# moodlamp.net
KiCad netlist of a schematic drawn in EAGLE
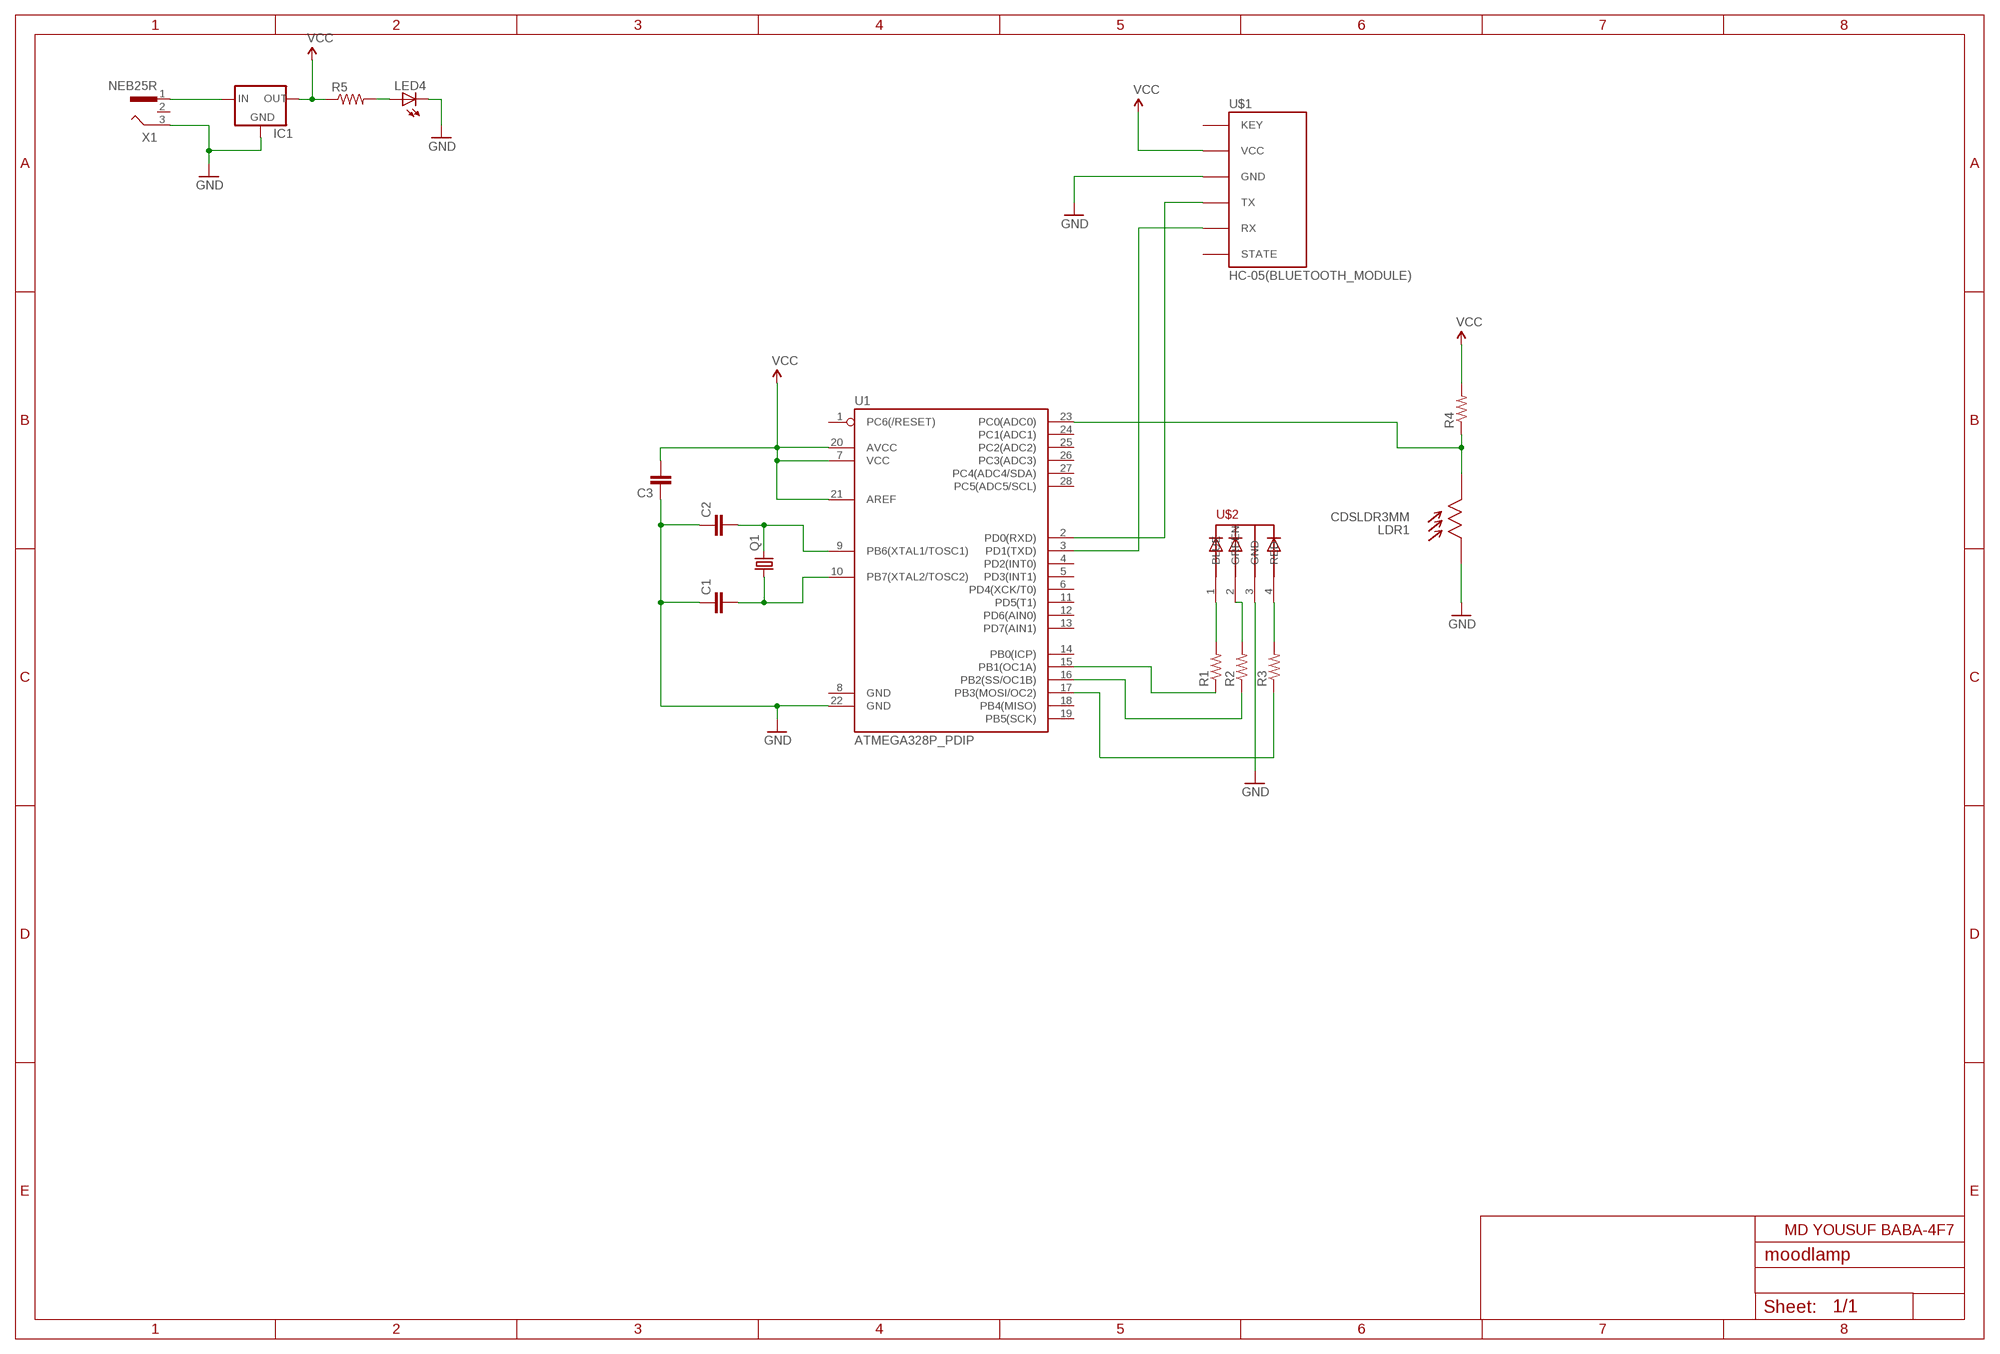
[diagram p0: schematic, sheet 1]

(export (version "E")
  (design (tool "Eeschema 10.0.6"))
  (components
    (comp (ref "C1")
      (value "C-EU025-024X044")
      (footprint "eagle-import:C025-024X044")
      (libsource (lib "eagle-import") (part "C-EU025-024X044"))
    )
    (comp (ref "C2")
      (value "C-EU025-024X044")
      (footprint "eagle-import:C025-024X044")
      (libsource (lib "eagle-import") (part "C-EU025-024X044"))
    )
    (comp (ref "C3")
      (value "C-EU025-024X044")
      (footprint "eagle-import:C025-024X044")
      (libsource (lib "eagle-import") (part "C-EU025-024X044"))
    )
    (comp (ref "IC1")
      (value "V_REG_78XX-TO-220")
      (footprint "eagle-import:TO-220-ALT")
      (libsource (lib "eagle-import") (part "V_REG_78XX-TO-220"))
    )
    (comp (ref "LDR1")
      (value "CDSLDR3MM")
      (footprint "eagle-import:LDR3MM")
      (libsource (lib "eagle-import") (part "CDSLDR3MM"))
    )
    (comp (ref "LED4")
      (value "LED3MM")
      (footprint "eagle-import:LED3MM")
      (libsource (lib "eagle-import") (part "LED3MM"))
    )
    (comp (ref "Q1")
      (value "CRYSTALHC49US")
      (footprint "eagle-import:HC49US")
      (libsource (lib "eagle-import") (part "CRYSTALHC49US"))
    )
    (comp (ref "R1")
      (value "RESISTOR0207/7")
      (footprint "eagle-import:0207_7")
      (libsource (lib "eagle-import") (part "RESISTOR0207/7"))
    )
    (comp (ref "R2")
      (value "RESISTOR0207/7")
      (footprint "eagle-import:0207_7")
      (libsource (lib "eagle-import") (part "RESISTOR0207/7"))
    )
    (comp (ref "R3")
      (value "RESISTOR0207/7")
      (footprint "eagle-import:0207_7")
      (libsource (lib "eagle-import") (part "RESISTOR0207/7"))
    )
    (comp (ref "R4")
      (value "RESISTOR0207/7")
      (footprint "eagle-import:0207_7")
      (libsource (lib "eagle-import") (part "RESISTOR0207/7"))
    )
    (comp (ref "R5")
      (value "RESISTOR0207/7")
      (footprint "eagle-import:0207_7")
      (libsource (lib "eagle-import") (part "RESISTOR0207/7"))
    )
    (comp (ref "U$1")
      (value "HC-05(BLUETOOTH_MODULE)")
      (footprint "eagle-import:HC-05")
      (libsource (lib "eagle-import") (part "HC-05(BLUETOOTH_MODULE)"))
    )
    (comp (ref "U$2")
      (value "5MMRGBLED")
      (footprint "eagle-import:LED5MMRGB")
      (libsource (lib "eagle-import") (part "5MMRGBLED"))
    )
    (comp (ref "U1")
      (value "ATMEGA328P_PDIP")
      (footprint "eagle-import:DIL28-3")
      (libsource (lib "eagle-import") (part "ATMEGA328P_PDIP"))
    )
    (comp (ref "X1")
      (value "NEB25R")
      (footprint "eagle-import:NEB25R")
      (libsource (lib "eagle-import") (part "NEB25R"))
    )
  )
  (nets
    (net (code "1") (name "GND") (class "Default")
      (node (ref "C1") (pin "1") (pinfunction "1_1") (pintype "passive"))
      (node (ref "C2") (pin "1") (pinfunction "1_1") (pintype "passive"))
      (node (ref "C3") (pin "1") (pinfunction "1_1") (pintype "passive"))
      (node (ref "IC1") (pin "GND") (pinfunction "GND_GND") (pintype "input"))
      (node (ref "LDR1") (pin "P$1") (pinfunction "P$1_P$1") (pintype "bidirectional"))
      (node (ref "LED4") (pin "K") (pinfunction "C_K") (pintype "passive"))
      (node (ref "U$1") (pin "GND") (pinfunction "GND_GND") (pintype "power_in"))
      (node (ref "U$2") (pin "3") (pinfunction "GND_3") (pintype "bidirectional"))
      (node (ref "U1") (pin "22") (pinfunction "GND_22") (pintype "bidirectional"))
      (node (ref "X1") (pin "3") (pinfunction "3_3") (pintype "passive"))
    )
    (net (code "2") (name "Net-(IC1-PadIN)") (class "Default")
      (node (ref "IC1") (pin "IN") (pinfunction "IN_IN") (pintype "input"))
      (node (ref "X1") (pin "1") (pinfunction "1_1") (pintype "passive"))
    )
    (net (code "3") (name "Net-(LED4-PadA)") (class "Default")
      (node (ref "LED4") (pin "A") (pinfunction "A_A") (pintype "passive"))
      (node (ref "R5") (pin "2") (pinfunction "2_2") (pintype "passive"))
    )
    (net (code "4") (name "Net-(U$2-BLUE)") (class "Default")
      (node (ref "R1") (pin "2") (pinfunction "2_2") (pintype "passive"))
      (node (ref "U$2") (pin "1") (pinfunction "BLUE_1") (pintype "bidirectional"))
    )
    (net (code "5") (name "Net-(U$2-GREEN)") (class "Default")
      (node (ref "R2") (pin "2") (pinfunction "2_2") (pintype "passive"))
      (node (ref "U$2") (pin "2") (pinfunction "GREEN_2") (pintype "bidirectional"))
    )
    (net (code "6") (name "Net-(U$2-RED)") (class "Default")
      (node (ref "R3") (pin "2") (pinfunction "2_2") (pintype "passive"))
      (node (ref "U$2") (pin "4") (pinfunction "RED_4") (pintype "bidirectional"))
    )
    (net (code "7") (name "Net-(U1-PB1(OC1A))") (class "Default")
      (node (ref "R1") (pin "1") (pinfunction "1_1") (pintype "passive"))
      (node (ref "U1") (pin "15") (pinfunction "PB1(OC1A)_15") (pintype "bidirectional"))
    )
    (net (code "8") (name "Net-(U1-PB2(SS{slash}OC1B))") (class "Default")
      (node (ref "R2") (pin "1") (pinfunction "1_1") (pintype "passive"))
      (node (ref "U1") (pin "16") (pinfunction "PB2(SS/OC1B)_16") (pintype "bidirectional"))
    )
    (net (code "9") (name "Net-(U1-PB3(MOSI{slash}OC2))") (class "Default")
      (node (ref "R3") (pin "1") (pinfunction "1_1") (pintype "passive"))
      (node (ref "U1") (pin "17") (pinfunction "PB3(MOSI/OC2)_17") (pintype "bidirectional"))
    )
    (net (code "10") (name "Net-(U1-PB6(XTAL1{slash}TOSC1))") (class "Default")
      (node (ref "C2") (pin "2") (pinfunction "2_2") (pintype "passive"))
      (node (ref "Q1") (pin "2") (pinfunction "2_2") (pintype "passive"))
      (node (ref "U1") (pin "9") (pinfunction "PB6(XTAL1/TOSC1)_9") (pintype "bidirectional"))
    )
    (net (code "11") (name "Net-(U1-PB7(XTAL2{slash}TOSC2))") (class "Default")
      (node (ref "C1") (pin "2") (pinfunction "2_2") (pintype "passive"))
      (node (ref "Q1") (pin "1") (pinfunction "1_1") (pintype "passive"))
      (node (ref "U1") (pin "10") (pinfunction "PB7(XTAL2/TOSC2)_10") (pintype "bidirectional"))
    )
    (net (code "12") (name "Net-(U1-PC0(ADC0))") (class "Default")
      (node (ref "LDR1") (pin "P$2") (pinfunction "P$2_P$2") (pintype "bidirectional"))
      (node (ref "R4") (pin "1") (pinfunction "1_1") (pintype "passive"))
      (node (ref "U1") (pin "23") (pinfunction "PC0(ADC0)_23") (pintype "bidirectional"))
    )
    (net (code "13") (name "Net-(U1-PD0(RXD))") (class "Default")
      (node (ref "U$1") (pin "TX") (pinfunction "TX_TX") (pintype "bidirectional"))
      (node (ref "U1") (pin "2") (pinfunction "PD0(RXD)_2") (pintype "bidirectional"))
    )
    (net (code "14") (name "Net-(U1-PD1(TXD))") (class "Default")
      (node (ref "U$1") (pin "RX") (pinfunction "RX_RX") (pintype "bidirectional"))
      (node (ref "U1") (pin "3") (pinfunction "PD1(TXD)_3") (pintype "bidirectional"))
    )
    (net (code "15") (name "VCC") (class "Default")
      (node (ref "C3") (pin "2") (pinfunction "2_2") (pintype "passive"))
      (node (ref "IC1") (pin "OUT") (pinfunction "OUT_OUT") (pintype "output"))
      (node (ref "R4") (pin "2") (pinfunction "2_2") (pintype "passive"))
      (node (ref "R5") (pin "1") (pinfunction "1_1") (pintype "passive"))
      (node (ref "U$1") (pin "VCC") (pinfunction "VCC_VCC") (pintype "power_in"))
      (node (ref "U1") (pin "20") (pinfunction "AVCC_20") (pintype "bidirectional"))
      (node (ref "U1") (pin "21") (pinfunction "AREF_21") (pintype "bidirectional"))
      (node (ref "U1") (pin "7") (pinfunction "VCC_7") (pintype "bidirectional"))
    )
    (net (code "16") (name "unconnected-(U$1-PadKEY)") (class "Default")
      (node (ref "U$1") (pin "KEY") (pinfunction "KEY_KEY") (pintype "bidirectional"))
    )
    (net (code "17") (name "unconnected-(U$1-PadSTATE)") (class "Default")
      (node (ref "U$1") (pin "STATE") (pinfunction "STATE_STATE") (pintype "bidirectional"))
    )
    (net (code "18") (name "unconnected-(U1-GND-Pad8)") (class "Default")
      (node (ref "U1") (pin "8") (pinfunction "GND_8") (pintype "bidirectional"))
    )
    (net (code "19") (name "unconnected-(U1-PB0(ICP)-Pad14)") (class "Default")
      (node (ref "U1") (pin "14") (pinfunction "PB0(ICP)_14") (pintype "bidirectional"))
    )
    (net (code "20") (name "unconnected-(U1-PB4(MISO)-Pad18)") (class "Default")
      (node (ref "U1") (pin "18") (pinfunction "PB4(MISO)_18") (pintype "bidirectional"))
    )
    (net (code "21") (name "unconnected-(U1-PB5(SCK)-Pad19)") (class "Default")
      (node (ref "U1") (pin "19") (pinfunction "PB5(SCK)_19") (pintype "bidirectional"))
    )
    (net (code "22") (name "unconnected-(U1-PC1(ADC1)-Pad24)") (class "Default")
      (node (ref "U1") (pin "24") (pinfunction "PC1(ADC1)_24") (pintype "bidirectional"))
    )
    (net (code "23") (name "unconnected-(U1-PC2(ADC2)-Pad25)") (class "Default")
      (node (ref "U1") (pin "25") (pinfunction "PC2(ADC2)_25") (pintype "bidirectional"))
    )
    (net (code "24") (name "unconnected-(U1-PC3(ADC3)-Pad26)") (class "Default")
      (node (ref "U1") (pin "26") (pinfunction "PC3(ADC3)_26") (pintype "bidirectional"))
    )
    (net (code "25") (name "unconnected-(U1-PC4(ADC4{slash}SDA)-Pad27)") (class "Default")
      (node (ref "U1") (pin "27") (pinfunction "PC4(ADC4/SDA)_27") (pintype "bidirectional"))
    )
    (net (code "26") (name "unconnected-(U1-PC5(ADC5{slash}SCL)-Pad28)") (class "Default")
      (node (ref "U1") (pin "28") (pinfunction "PC5(ADC5/SCL)_28") (pintype "bidirectional"))
    )
    (net (code "27") (name "unconnected-(U1-PC6({slash}RESET)-Pad1)") (class "Default")
      (node (ref "U1") (pin "1") (pinfunction "PC6(/RESET)_1") (pintype "bidirectional"))
    )
    (net (code "28") (name "unconnected-(U1-PD2(INT0)-Pad4)") (class "Default")
      (node (ref "U1") (pin "4") (pinfunction "PD2(INT0)_4") (pintype "bidirectional"))
    )
    (net (code "29") (name "unconnected-(U1-PD3(INT1)-Pad5)") (class "Default")
      (node (ref "U1") (pin "5") (pinfunction "PD3(INT1)_5") (pintype "bidirectional"))
    )
    (net (code "30") (name "unconnected-(U1-PD4(XCK{slash}T0)-Pad6)") (class "Default")
      (node (ref "U1") (pin "6") (pinfunction "PD4(XCK/T0)_6") (pintype "bidirectional"))
    )
    (net (code "31") (name "unconnected-(U1-PD5(T1)-Pad11)") (class "Default")
      (node (ref "U1") (pin "11") (pinfunction "PD5(T1)_11") (pintype "bidirectional"))
    )
    (net (code "32") (name "unconnected-(U1-PD6(AIN0)-Pad12)") (class "Default")
      (node (ref "U1") (pin "12") (pinfunction "PD6(AIN0)_12") (pintype "bidirectional"))
    )
    (net (code "33") (name "unconnected-(U1-PD7(AIN1)-Pad13)") (class "Default")
      (node (ref "U1") (pin "13") (pinfunction "PD7(AIN1)_13") (pintype "bidirectional"))
    )
    (net (code "34") (name "unconnected-(X1-Pad2)") (class "Default")
      (node (ref "X1") (pin "2") (pinfunction "2_2") (pintype "passive"))
    )
  )
)
